# panel_power_backlight.net
KiCad netlist of a schematic drawn in Altium Designer
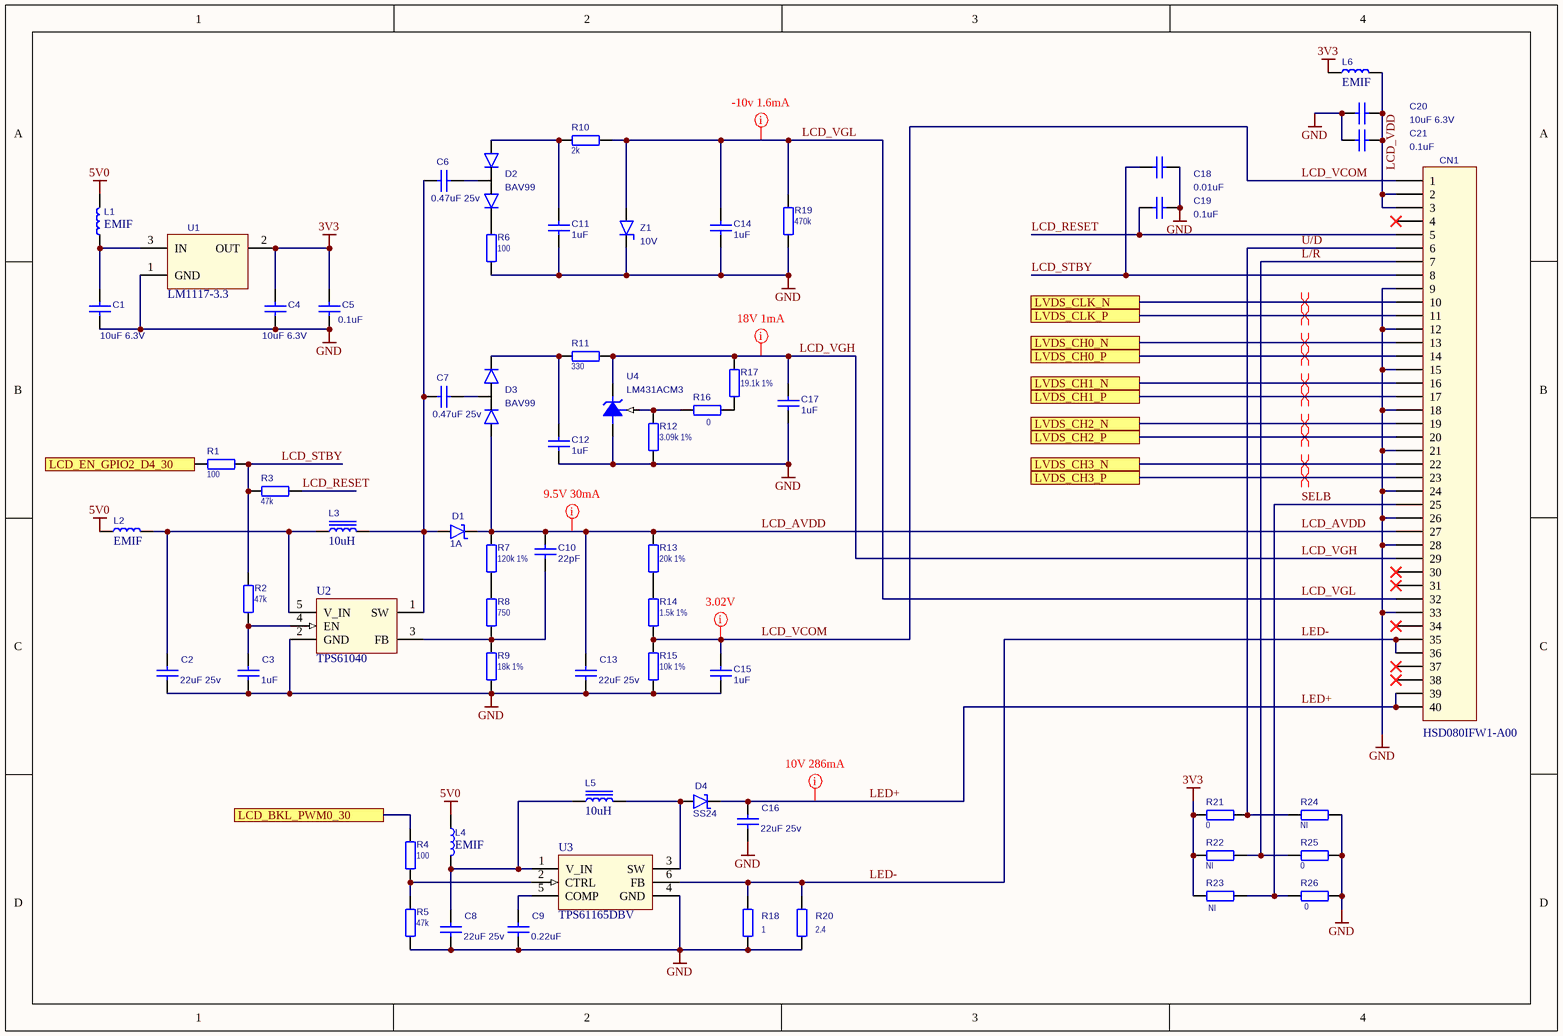
[diagram p0: panel_power_backlight.SchDoc]

(export (version "E")
  (design (tool "Eeschema 10.0.6"))
  (components
    (comp (ref "C1")
      (value "10uF 6.3V")
      (footprint "Capacitors:C0603")
      (description "CAP_NPOL")
      (fields (field (name "Comment") "CC0603MRX5R5BB106"))
      (libsource (lib "capacitors") (part "CAP_NPOL"))
    )
    (comp (ref "C2")
      (value "22uF 25v")
      (footprint "Capacitors:C0805")
      (description "CAP_NPOL")
      (fields (field (name "Comment") "CL21A226MAQNNNE"))
      (libsource (lib "capacitors") (part "CAP_NPOL"))
    )
    (comp (ref "C3")
      (value "1uF")
      (footprint "Capacitors:C0603")
      (description "CAP_NPOL")
      (fields (field (name "Comment") "CC0603KRX7R9BB105"))
      (libsource (lib "capacitors") (part "CAP_NPOL"))
    )
    (comp (ref "C4")
      (value "10uF 6.3V")
      (footprint "Capacitors:C0603")
      (description "CAP_NPOL")
      (fields (field (name "Comment") "CC0603MRX5R5BB106"))
      (libsource (lib "capacitors") (part "CAP_NPOL"))
    )
    (comp (ref "C5")
      (value "0.1uF")
      (footprint "C0603")
      (description "CAP_NPOL")
      (fields (field (name "Comment") "C1608X7R1H104K080AA"))
      (libsource (lib "capacitors") (part "CAP_NPOL"))
    )
    (comp (ref "C6")
      (value "0.47uF 25v")
      (footprint "Capacitors:C0603")
      (description "CAP_NPOL")
      (fields (field (name "Comment") "GRM188R71E474KA12D"))
      (libsource (lib "capacitors") (part "CAP_NPOL"))
    )
    (comp (ref "C7")
      (value "0.47uF 25v")
      (footprint "Capacitors:C0603")
      (description "CAP_NPOL")
      (fields (field (name "Comment") "GRM188R71E474KA12D"))
      (libsource (lib "capacitors") (part "CAP_NPOL"))
    )
    (comp (ref "C8")
      (value "22uF 25v")
      (footprint "Capacitors:C0805")
      (description "CAP_NPOL")
      (fields (field (name "Comment") "CL21A226MAQNNNE"))
      (libsource (lib "capacitors") (part "CAP_NPOL"))
    )
    (comp (ref "C9")
      (value "0.22uF")
      (footprint "Capacitors:C0603")
      (description "CAP_NPOL")
      (fields (field (name "Comment") "CC0603ZRY5V8BB224"))
      (libsource (lib "capacitors") (part "CAP_NPOL"))
    )
    (comp (ref "C10")
      (value "22pF")
      (footprint "Capacitors:C0603")
      (description "CAP_NPOL")
      (fields (field (name "Comment") "CL10C220JB8NNNC"))
      (libsource (lib "capacitors") (part "CAP_NPOL"))
    )
    (comp (ref "C11")
      (value "1uF")
      (footprint "C0603")
      (description "CAP_NPOL")
      (fields (field (name "Comment") "CC0603KRX7R9BB105"))
      (libsource (lib "capacitors") (part "CAP_NPOL"))
    )
    (comp (ref "C12")
      (value "1uF")
      (footprint "C0603")
      (description "CAP_NPOL")
      (fields (field (name "Comment") "CC0603KRX7R9BB105"))
      (libsource (lib "capacitors") (part "CAP_NPOL"))
    )
    (comp (ref "C13")
      (value "22uF 25v")
      (footprint "Capacitors:C0805")
      (description "CAP_NPOL")
      (fields (field (name "Comment") "CL21A226MAQNNNE"))
      (libsource (lib "capacitors") (part "CAP_NPOL"))
    )
    (comp (ref "C14")
      (value "1uF")
      (footprint "C0603")
      (description "CAP_NPOL")
      (fields (field (name "Comment") "CC0603KRX7R9BB105"))
      (libsource (lib "capacitors") (part "CAP_NPOL"))
    )
    (comp (ref "C15")
      (value "1uF")
      (footprint "C0603")
      (description "CAP_NPOL")
      (fields (field (name "Comment") "CC0603KRX7R9BB105"))
      (libsource (lib "capacitors") (part "CAP_NPOL"))
    )
    (comp (ref "C16")
      (value "22uF 25v")
      (footprint "Capacitors:C0805")
      (description "CAP_NPOL")
      (fields (field (name "Comment") "CL21A226MAQNNNE"))
      (libsource (lib "capacitors") (part "CAP_NPOL"))
    )
    (comp (ref "C17")
      (value "1uF")
      (footprint "C0603")
      (description "CAP_NPOL")
      (fields (field (name "Comment") "CC0603KRX7R9BB105"))
      (libsource (lib "capacitors") (part "CAP_NPOL"))
    )
    (comp (ref "C18")
      (value "0.01uF")
      (footprint "C0603")
      (description "CAP_NPOL")
      (fields (field (name "Comment") "CL10B103KB8NNNC"))
      (libsource (lib "capacitors") (part "CAP_NPOL"))
    )
    (comp (ref "C19")
      (value "0.1uF")
      (footprint "C0603")
      (description "CAP_NPOL")
      (fields (field (name "Comment") "C1608X7R1H104K080AA"))
      (libsource (lib "capacitors") (part "CAP_NPOL"))
    )
    (comp (ref "C20")
      (value "10uF 6.3V")
      (footprint "Capacitors:C0603")
      (description "CAP_NPOL")
      (fields (field (name "Comment") "CC0603MRX5R5BB106"))
      (libsource (lib "capacitors") (part "CAP_NPOL"))
    )
    (comp (ref "C21")
      (value "0.1uF")
      (footprint "C0603")
      (description "CAP_NPOL")
      (fields (field (name "Comment") "C1608X7R1H104K080AA"))
      (libsource (lib "capacitors") (part "CAP_NPOL"))
    )
    (comp (ref "CN1")
      (value "HSD080IFW1-A00")
      (footprint "40S-0.5SH")
      (description "DT38")
      (fields (field (name "Comment") "FH12-40"))
      (libsource (lib "FPC_FH12-40S-0.5SH") (part "FH12-40"))
    )
    (comp (ref "D1")
      (value "1A")
      (footprint "Diodes:SOD-323")
      (description "SHOTTKY")
      (fields (field (name "Comment") "PMEG2010EJ.115"))
      (libsource (lib "diodes") (part "SHOTTKY"))
    )
    (comp (ref "D2")
      (value "BAV99")
      (footprint "SOT-23-3")
      (description "Dual series 1")
      (fields (field (name "Comment") "BAV99.215"))
      (libsource (lib "diodes") (part "DIODE_DUAL_1"))
    )
    (comp (ref "D3")
      (value "BAV99")
      (footprint "SOT-23-3")
      (description "Dual series 1")
      (fields (field (name "Comment") "BAV99.215"))
      (libsource (lib "diodes") (part "DIODE_DUAL_1"))
    )
    (comp (ref "D4")
      (value "SS24")
      (footprint "SMA")
      (description "SHOTTKY")
      (libsource (lib "diodes") (part "SHOTTKY"))
    )
    (comp (ref "L1")
      (value "EMIF")
      (footprint "IND0805")
      (description "IND_WO_IRON")
      (fields (field (name "Comment") "BLM21PG221SN1D"))
      (libsource (lib "") (part "IND_WO_IRON_1"))
    )
    (comp (ref "L2")
      (value "EMIF")
      (footprint "IND0805")
      (description "IND_WO_IRON")
      (fields (field (name "Comment") "BLM21PG221SN1D"))
      (libsource (lib "inductors") (part "IND_WO_IRON"))
    )
    (comp (ref "L3")
      (value "10uH")
      (footprint "CDRH3D16")
      (description "IND_W_IRON")
      (fields (field (name "Comment") "CDRH3D16NP-100NC"))
      (libsource (lib "inductors") (part "IND_W_IRON"))
    )
    (comp (ref "L4")
      (value "EMIF")
      (footprint "IND0805")
      (description "IND_WO_IRON")
      (fields (field (name "Comment") "BLM21PG221SN1D"))
      (libsource (lib "inductors") (part "IND_WO_IRON"))
    )
    (comp (ref "L5")
      (value "10uH")
      (footprint "CDRH6D28")
      (description "IND_W_IRON")
      (fields (field (name "Comment") "CDRH6D28-100NC"))
      (libsource (lib "inductors") (part "IND_W_IRON"))
    )
    (comp (ref "L6")
      (value "EMIF")
      (footprint "IND0805")
      (description "IND_WO_IRON")
      (fields (field (name "Comment") "BLM21PG221SN1D"))
      (libsource (lib "") (part "IND_WO_IRON_1"))
    )
    (comp (ref "R1") (value "100") (footprint "R0603") (libsource (lib "resistors") (part "RESISTOR")))
    (comp (ref "R2")
      (value "47k")
      (footprint "R0603")
      (description "RES")
      (libsource (lib "resistors") (part "RESISTOR"))
    )
    (comp (ref "R3")
      (value "47k")
      (footprint "R0603")
      (description "RES")
      (libsource (lib "resistors") (part "RESISTOR"))
    )
    (comp (ref "R4") (value "100") (footprint "R0603") (libsource (lib "resistors") (part "RESISTOR")))
    (comp (ref "R5")
      (value "47k")
      (footprint "R0603")
      (description "RES")
      (libsource (lib "resistors") (part "RESISTOR"))
    )
    (comp (ref "R6")
      (value "100")
      (footprint "R0603")
      (description "RES")
      (libsource (lib "resistors") (part "RESISTOR"))
    )
    (comp (ref "R7")
      (value "120k 1%")
      (footprint "R0603")
      (description "RES")
      (fields (field (name "Comment") "120k"))
      (libsource (lib "resistors") (part "RESISTOR"))
    )
    (comp (ref "R8")
      (value "750")
      (footprint "R0603")
      (description "RES")
      (libsource (lib "resistors") (part "RESISTOR"))
    )
    (comp (ref "R9")
      (value "18k 1%")
      (footprint "R0603")
      (description "RES")
      (fields (field (name "Comment") "18k"))
      (libsource (lib "resistors") (part "RESISTOR"))
    )
    (comp (ref "R10")
      (value "2k")
      (footprint "R0603")
      (description "RES")
      (libsource (lib "resistors") (part "RESISTOR"))
    )
    (comp (ref "R11")
      (value "330")
      (footprint "R0603")
      (description "RES")
      (libsource (lib "resistors") (part "RESISTOR"))
    )
    (comp (ref "R12")
      (value "3.09k 1%")
      (footprint "R0603")
      (description "RES")
      (fields (field (name "Comment") "3.09k"))
      (libsource (lib "resistors") (part "RESISTOR"))
    )
    (comp (ref "R13")
      (value "20k 1%")
      (footprint "Resistors:R0603")
      (description "RES")
      (fields (field (name "Comment") "RC0603FR-0720KL"))
      (libsource (lib "resistors") (part "RESISTOR"))
    )
    (comp (ref "R14")
      (value "1.5k 1%")
      (footprint "R0603")
      (description "RES")
      (fields (field (name "Comment") "RC0603FR-071K5L"))
      (libsource (lib "resistors") (part "RESISTOR"))
    )
    (comp (ref "R15")
      (value "10k 1%")
      (footprint "R0603")
      (description "RES")
      (fields (field (name "Comment") "RC0603FR-0710KL"))
      (libsource (lib "resistors") (part "RESISTOR"))
    )
    (comp (ref "R16")
      (value "0")
      (footprint "R0603")
      (description "RES")
      (libsource (lib "resistors") (part "RESISTOR"))
    )
    (comp (ref "R17")
      (value "19.1k 1%")
      (footprint "R0603")
      (description "RES")
      (libsource (lib "resistors") (part "RESISTOR"))
    )
    (comp (ref "R18")
      (value "1")
      (footprint "R0805")
      (description "RES")
      (fields (field (name "Comment") "RC0805FR-071RL"))
      (libsource (lib "resistors") (part "RESISTOR"))
    )
    (comp (ref "R19")
      (value "470k")
      (footprint "R0603")
      (description "RES")
      (libsource (lib "resistors") (part "RESISTOR"))
    )
    (comp (ref "R20")
      (value "2.4")
      (footprint "R0805")
      (description "RES")
      (fields (field (name "Comment") "RES 0805 2R4 5%"))
      (libsource (lib "resistors") (part "RESISTOR"))
    )
    (comp (ref "R21")
      (value "0")
      (footprint "R0603")
      (description "RES")
      (libsource (lib "resistors") (part "RESISTOR"))
    )
    (comp (ref "R22")
      (value "NI")
      (footprint "R0603")
      (description "RES")
      (fields (field (name "Comment") "DNI"))
      (libsource (lib "resistors") (part "RESISTOR"))
    )
    (comp (ref "R23")
      (value "NI")
      (footprint "R0603")
      (description "RES")
      (fields (field (name "Comment") "DNI"))
      (libsource (lib "resistors") (part "RESISTOR"))
    )
    (comp (ref "R24")
      (value "NI")
      (footprint "R0603")
      (description "RES")
      (fields (field (name "Comment") "DNI"))
      (libsource (lib "resistors") (part "RESISTOR"))
    )
    (comp (ref "R25")
      (value "0")
      (footprint "R0603")
      (description "RES")
      (libsource (lib "resistors") (part "RESISTOR"))
    )
    (comp (ref "R26")
      (value "0")
      (footprint "R0603")
      (description "RES")
      (libsource (lib "resistors") (part "RESISTOR"))
    )
    (comp (ref "U1")
      (value "LM1117-3.3")
      (footprint "SOT-223")
      (description "LM1117")
      (libsource (lib "LM1117") (part "LM1117"))
    )
    (comp (ref "U2") (value "TPS61040") (footprint "SOT-23-5") (libsource (lib "TPS6104x") (part "TPS6104x")))
    (comp (ref "U3")
      (value "TPS61165DBV")
      (footprint "SOT-23-6")
      (description "TPS61165DBV (SOT-23-6 package)")
      (fields (field (name "Comment") "TPS61165"))
      (libsource (lib "TPS61165") (part "TPS61165DBV"))
    )
    (comp (ref "U4")
      (value "LM431ACM3")
      (footprint "SOT-23-3")
      (description "Adjustable Precision Zener Shunt Regulator, 3-pin SOT-23")
      (fields
        (field (name "MANUFACTURER") "National Semiconductor")
        (field (name "PUBLISHER") "Altium Limited")
      )
      (libsource (lib "NSC MiscPower") (part "LM431ACM3"))
    )
    (comp (ref "Z1")
      (value "10V")
      (footprint "SOD-80C")
      (description "ZENNER")
      (fields (field (name "Comment") "BZV55-C10.115"))
      (libsource (lib "diodes") (part "ZENNER"))
    )
  )
  (nets
    (net (code "1") (name "/LCD_AVDD") (class "Default")
      (node (ref "C10") (pin "1") (pinfunction "1_1") (pintype "passive"))
      (node (ref "C13") (pin "2") (pinfunction "2_2") (pintype "passive"))
      (node (ref "CN1") (pin "27") (pinfunction "27_27") (pintype "passive"))
      (node (ref "D1") (pin "2") (pinfunction "K_2") (pintype "passive"))
      (node (ref "D3") (pin "1") (pinfunction "A_1") (pintype "passive"))
      (node (ref "R13") (pin "2") (pinfunction "2_2") (pintype "passive"))
      (node (ref "R7") (pin "2") (pinfunction "2_2") (pintype "passive"))
    )
    (net (code "2") (name "/LCD_BKL_PWM0_30") (class "Default")
      (node (ref "R4") (pin "2") (pinfunction "2_2") (pintype "passive"))
    )
    (net (code "3") (name "/LCD_EN_GPIO2_D4_30") (class "Default")
      (node (ref "R1") (pin "2") (pinfunction "2_2") (pintype "passive"))
    )
    (net (code "4") (name "/LCD_RESET") (class "Default")
      (node (ref "C19") (pin "2") (pinfunction "2_2") (pintype "passive"))
      (node (ref "CN1") (pin "5") (pinfunction "5_5") (pintype "passive"))
      (node (ref "R3") (pin "1") (pinfunction "1_1") (pintype "passive"))
    )
    (net (code "5") (name "/LCD_STBY") (class "Default")
      (node (ref "C18") (pin "2") (pinfunction "2_2") (pintype "passive"))
      (node (ref "CN1") (pin "8") (pinfunction "8_8") (pintype "passive"))
      (node (ref "R1") (pin "1") (pinfunction "1_1") (pintype "passive"))
      (node (ref "R2") (pin "2") (pinfunction "2_2") (pintype "passive"))
      (node (ref "R3") (pin "2") (pinfunction "2_2") (pintype "passive"))
    )
    (net (code "6") (name "/LCD_VCOM") (class "Default")
      (node (ref "C15") (pin "2") (pinfunction "2_2") (pintype "passive"))
      (node (ref "CN1") (pin "1") (pinfunction "1_1") (pintype "passive"))
      (node (ref "R14") (pin "1") (pinfunction "1_1") (pintype "passive"))
      (node (ref "R15") (pin "2") (pinfunction "2_2") (pintype "passive"))
    )
    (net (code "7") (name "/LCD_VDD") (class "Default")
      (node (ref "C20") (pin "2") (pinfunction "2_2") (pintype "passive"))
      (node (ref "C21") (pin "1") (pinfunction "1_1") (pintype "passive"))
      (node (ref "CN1") (pin "2") (pinfunction "2_2") (pintype "passive"))
      (node (ref "CN1") (pin "3") (pinfunction "3_3") (pintype "passive"))
      (node (ref "L6") (pin "2") (pintype "passive"))
    )
    (net (code "8") (name "/LCD_VGH") (class "Default")
      (node (ref "C17") (pin "2") (pinfunction "2_2") (pintype "passive"))
      (node (ref "CN1") (pin "29") (pinfunction "29_29") (pintype "passive"))
      (node (ref "R11") (pin "2") (pinfunction "2_2") (pintype "passive"))
      (node (ref "R17") (pin "2") (pinfunction "2_2") (pintype "passive"))
      (node (ref "U4") (pin "1") (pinfunction "K_1") (pintype "passive"))
    )
    (net (code "9") (name "/LCD_VGL") (class "Default")
      (node (ref "C14") (pin "2") (pinfunction "2_2") (pintype "passive"))
      (node (ref "CN1") (pin "32") (pinfunction "32_32") (pintype "passive"))
      (node (ref "R10") (pin "2") (pinfunction "2_2") (pintype "passive"))
      (node (ref "R19") (pin "2") (pinfunction "2_2") (pintype "passive"))
      (node (ref "Z1") (pin "1") (pinfunction "A_1") (pintype "passive"))
    )
    (net (code "10") (name "/LED+") (class "Default")
      (node (ref "C16") (pin "2") (pinfunction "2_2") (pintype "passive"))
      (node (ref "CN1") (pin "39") (pinfunction "39_39") (pintype "passive"))
      (node (ref "CN1") (pin "40") (pinfunction "40_40") (pintype "passive"))
      (node (ref "D4") (pin "2") (pinfunction "K_2") (pintype "passive"))
    )
    (net (code "11") (name "/LED-") (class "Default")
      (node (ref "CN1") (pin "35") (pinfunction "35_35") (pintype "passive"))
      (node (ref "CN1") (pin "36") (pinfunction "36_36") (pintype "passive"))
      (node (ref "R18") (pin "2") (pinfunction "2_2") (pintype "passive"))
      (node (ref "R20") (pin "2") (pinfunction "2_2") (pintype "passive"))
      (node (ref "U3") (pin "6") (pinfunction "FB_6") (pintype "passive"))
    )
    (net (code "12") (name "/LVDS_CH0_N") (class "Default")
      (node (ref "CN1") (pin "13") (pinfunction "13_13") (pintype "passive"))
    )
    (net (code "13") (name "/LVDS_CH0_P") (class "Default")
      (node (ref "CN1") (pin "14") (pinfunction "14_14") (pintype "passive"))
    )
    (net (code "14") (name "/LVDS_CH1_N") (class "Default")
      (node (ref "CN1") (pin "16") (pinfunction "16_16") (pintype "passive"))
    )
    (net (code "15") (name "/LVDS_CH1_P") (class "Default")
      (node (ref "CN1") (pin "17") (pinfunction "17_17") (pintype "passive"))
    )
    (net (code "16") (name "/LVDS_CH2_N") (class "Default")
      (node (ref "CN1") (pin "19") (pinfunction "19_19") (pintype "passive"))
    )
    (net (code "17") (name "/LVDS_CH2_P") (class "Default")
      (node (ref "CN1") (pin "20") (pinfunction "20_20") (pintype "passive"))
    )
    (net (code "18") (name "/LVDS_CH3_N") (class "Default")
      (node (ref "CN1") (pin "22") (pinfunction "22_22") (pintype "passive"))
    )
    (net (code "19") (name "/LVDS_CH3_P") (class "Default")
      (node (ref "CN1") (pin "23") (pinfunction "23_23") (pintype "passive"))
    )
    (net (code "20") (name "/LVDS_CLK_N") (class "Default")
      (node (ref "CN1") (pin "10") (pinfunction "10_10") (pintype "passive"))
    )
    (net (code "21") (name "/LVDS_CLK_P") (class "Default")
      (node (ref "CN1") (pin "11") (pinfunction "11_11") (pintype "passive"))
    )
    (net (code "22") (name "/L{slash}R") (class "Default")
      (node (ref "CN1") (pin "7") (pinfunction "7_7") (pintype "passive"))
      (node (ref "R22") (pin "2") (pinfunction "2_2") (pintype "passive"))
      (node (ref "R25") (pin "1") (pinfunction "1_1") (pintype "passive"))
    )
    (net (code "23") (name "/SELB") (class "Default")
      (node (ref "CN1") (pin "25") (pinfunction "25_25") (pintype "passive"))
      (node (ref "R23") (pin "2") (pinfunction "2_2") (pintype "passive"))
      (node (ref "R26") (pin "1") (pinfunction "1_1") (pintype "passive"))
    )
    (net (code "24") (name "/U{slash}D") (class "Default")
      (node (ref "CN1") (pin "6") (pinfunction "6_6") (pintype "passive"))
      (node (ref "R21") (pin "2") (pinfunction "2_2") (pintype "passive"))
      (node (ref "R24") (pin "1") (pinfunction "1_1") (pintype "passive"))
    )
    (net (code "25") (name "3V3") (class "Default")
      (node (ref "C4") (pin "1") (pinfunction "1_1") (pintype "passive"))
      (node (ref "C5") (pin "2") (pinfunction "2_2") (pintype "passive"))
      (node (ref "L6") (pin "1") (pintype "passive"))
      (node (ref "R21") (pin "1") (pinfunction "1_1") (pintype "passive"))
      (node (ref "R22") (pin "1") (pinfunction "1_1") (pintype "passive"))
      (node (ref "R23") (pin "1") (pinfunction "1_1") (pintype "passive"))
      (node (ref "U1") (pin "2") (pinfunction "OUT_2") (pintype "passive"))
    )
    (net (code "26") (name "5V0") (class "Default")
      (node (ref "L1") (pin "2") (pintype "passive"))
      (node (ref "L2") (pin "2") (pintype "passive"))
      (node (ref "L4") (pin "2") (pintype "passive"))
    )
    (net (code "27") (name "GND") (class "Default")
      (node (ref "C1") (pin "2") (pinfunction "2_2") (pintype "passive"))
      (node (ref "C11") (pin "1") (pinfunction "1_1") (pintype "passive"))
      (node (ref "C12") (pin "1") (pinfunction "1_1") (pintype "passive"))
      (node (ref "C13") (pin "1") (pinfunction "1_1") (pintype "passive"))
      (node (ref "C14") (pin "1") (pinfunction "1_1") (pintype "passive"))
      (node (ref "C15") (pin "1") (pinfunction "1_1") (pintype "passive"))
      (node (ref "C16") (pin "1") (pinfunction "1_1") (pintype "passive"))
      (node (ref "C17") (pin "1") (pinfunction "1_1") (pintype "passive"))
      (node (ref "C18") (pin "1") (pinfunction "1_1") (pintype "passive"))
      (node (ref "C19") (pin "1") (pinfunction "1_1") (pintype "passive"))
      (node (ref "C2") (pin "1") (pinfunction "1_1") (pintype "passive"))
      (node (ref "C20") (pin "1") (pinfunction "1_1") (pintype "passive"))
      (node (ref "C21") (pin "2") (pinfunction "2_2") (pintype "passive"))
      (node (ref "C3") (pin "1") (pinfunction "1_1") (pintype "passive"))
      (node (ref "C4") (pin "2") (pinfunction "2_2") (pintype "passive"))
      (node (ref "C5") (pin "1") (pinfunction "1_1") (pintype "passive"))
      (node (ref "C8") (pin "1") (pinfunction "1_1") (pintype "passive"))
      (node (ref "C9") (pin "1") (pinfunction "1_1") (pintype "passive"))
      (node (ref "CN1") (pin "12") (pinfunction "12_12") (pintype "passive"))
      (node (ref "CN1") (pin "15") (pinfunction "15_15") (pintype "passive"))
      (node (ref "CN1") (pin "18") (pinfunction "18_18") (pintype "passive"))
      (node (ref "CN1") (pin "21") (pinfunction "21_21") (pintype "passive"))
      (node (ref "CN1") (pin "24") (pinfunction "24_24") (pintype "passive"))
      (node (ref "CN1") (pin "26") (pinfunction "26_26") (pintype "passive"))
      (node (ref "CN1") (pin "28") (pinfunction "28_28") (pintype "passive"))
      (node (ref "CN1") (pin "33") (pinfunction "33_33") (pintype "passive"))
      (node (ref "CN1") (pin "9") (pinfunction "9_9") (pintype "passive"))
      (node (ref "R12") (pin "1") (pinfunction "1_1") (pintype "passive"))
      (node (ref "R15") (pin "1") (pinfunction "1_1") (pintype "passive"))
      (node (ref "R18") (pin "1") (pinfunction "1_1") (pintype "passive"))
      (node (ref "R19") (pin "1") (pinfunction "1_1") (pintype "passive"))
      (node (ref "R20") (pin "1") (pinfunction "1_1") (pintype "passive"))
      (node (ref "R24") (pin "2") (pinfunction "2_2") (pintype "passive"))
      (node (ref "R25") (pin "2") (pinfunction "2_2") (pintype "passive"))
      (node (ref "R26") (pin "2") (pinfunction "2_2") (pintype "passive"))
      (node (ref "R5") (pin "1") (pinfunction "1_1") (pintype "passive"))
      (node (ref "R6") (pin "2") (pinfunction "2_2") (pintype "passive"))
      (node (ref "R9") (pin "1") (pinfunction "1_1") (pintype "passive"))
      (node (ref "U1") (pin "1") (pinfunction "GND_1") (pintype "passive"))
      (node (ref "U2") (pin "2") (pinfunction "GND_2") (pintype "power_in"))
      (node (ref "U3") (pin "4") (pinfunction "GND_4") (pintype "power_in"))
      (node (ref "U4") (pin "3") (pinfunction "A_3") (pintype "passive"))
      (node (ref "Z1") (pin "2") (pinfunction "K_2") (pintype "passive"))
    )
    (net (code "28") (name "Net-(D1-A)") (class "Default")
      (node (ref "C6") (pin "2") (pinfunction "2_2") (pintype "passive"))
      (node (ref "C7") (pin "2") (pinfunction "2_2") (pintype "passive"))
      (node (ref "D1") (pin "1") (pinfunction "A_1") (pintype "passive"))
      (node (ref "L3") (pin "2") (pintype "passive"))
      (node (ref "U2") (pin "1") (pinfunction "SW_1") (pintype "passive"))
    )
    (net (code "29") (name "Net-(D2-A)") (class "Default")
      (node (ref "C11") (pin "2") (pinfunction "2_2") (pintype "passive"))
      (node (ref "D2") (pin "1") (pinfunction "A_1") (pintype "passive"))
      (node (ref "R10") (pin "1") (pinfunction "1_1") (pintype "passive"))
    )
    (net (code "30") (name "Net-(D2-A+K)") (class "Default")
      (node (ref "C6") (pin "1") (pinfunction "1_1") (pintype "passive"))
      (node (ref "D2") (pin "3") (pinfunction "A+K_3") (pintype "passive"))
    )
    (net (code "31") (name "Net-(D2-K)") (class "Default")
      (node (ref "D2") (pin "2") (pinfunction "K_2") (pintype "passive"))
      (node (ref "R6") (pin "1") (pinfunction "1_1") (pintype "passive"))
    )
    (net (code "32") (name "Net-(D3-A+K)") (class "Default")
      (node (ref "C7") (pin "1") (pinfunction "1_1") (pintype "passive"))
      (node (ref "D3") (pin "3") (pinfunction "A+K_3") (pintype "passive"))
    )
    (net (code "33") (name "Net-(D3-K)") (class "Default")
      (node (ref "C12") (pin "2") (pinfunction "2_2") (pintype "passive"))
      (node (ref "D3") (pin "2") (pinfunction "K_2") (pintype "passive"))
      (node (ref "R11") (pin "1") (pinfunction "1_1") (pintype "passive"))
    )
    (net (code "34") (name "Net-(D4-A)") (class "Default")
      (node (ref "D4") (pin "1") (pinfunction "A_1") (pintype "passive"))
      (node (ref "L5") (pin "2") (pintype "passive"))
      (node (ref "U3") (pin "3") (pinfunction "SW_3") (pintype "passive"))
    )
    (net (code "35") (name "Net-(R7-Pad1)") (class "Default")
      (node (ref "R7") (pin "1") (pinfunction "1_1") (pintype "passive"))
      (node (ref "R8") (pin "2") (pinfunction "2_2") (pintype "passive"))
    )
    (net (code "36") (name "Net-(R13-Pad1)") (class "Default")
      (node (ref "R13") (pin "1") (pinfunction "1_1") (pintype "passive"))
      (node (ref "R14") (pin "2") (pinfunction "2_2") (pintype "passive"))
    )
    (net (code "37") (name "Net-(R16-Pad1)") (class "Default")
      (node (ref "R16") (pin "1") (pinfunction "1_1") (pintype "passive"))
      (node (ref "R17") (pin "1") (pinfunction "1_1") (pintype "passive"))
    )
    (net (code "38") (name "Net-(U1-IN)") (class "Default")
      (node (ref "C1") (pin "1") (pinfunction "1_1") (pintype "passive"))
      (node (ref "L1") (pin "1") (pintype "passive"))
      (node (ref "U1") (pin "3") (pinfunction "IN_3") (pintype "passive"))
    )
    (net (code "39") (name "Net-(U2-EN)") (class "Default")
      (node (ref "C3") (pin "2") (pinfunction "2_2") (pintype "passive"))
      (node (ref "R2") (pin "1") (pinfunction "1_1") (pintype "passive"))
      (node (ref "U2") (pin "4") (pinfunction "EN_4") (pintype "input"))
    )
    (net (code "40") (name "Net-(U2-FB)") (class "Default")
      (node (ref "C10") (pin "2") (pinfunction "2_2") (pintype "passive"))
      (node (ref "R8") (pin "1") (pinfunction "1_1") (pintype "passive"))
      (node (ref "R9") (pin "2") (pinfunction "2_2") (pintype "passive"))
      (node (ref "U2") (pin "3") (pinfunction "FB_3") (pintype "passive"))
    )
    (net (code "41") (name "Net-(U2-V_IN)") (class "Default")
      (node (ref "C2") (pin "2") (pinfunction "2_2") (pintype "passive"))
      (node (ref "L2") (pin "1") (pintype "passive"))
      (node (ref "L3") (pin "1") (pintype "passive"))
      (node (ref "U2") (pin "5") (pinfunction "V_IN_5") (pintype "power_in"))
    )
    (net (code "42") (name "Net-(U3-COMP)") (class "Default")
      (node (ref "C9") (pin "2") (pinfunction "2_2") (pintype "passive"))
      (node (ref "U3") (pin "5") (pinfunction "COMP_5") (pintype "passive"))
    )
    (net (code "43") (name "Net-(U3-CTRL)") (class "Default")
      (node (ref "R4") (pin "1") (pinfunction "1_1") (pintype "passive"))
      (node (ref "R5") (pin "2") (pinfunction "2_2") (pintype "passive"))
      (node (ref "U3") (pin "2") (pinfunction "CTRL_2") (pintype "input"))
    )
    (net (code "44") (name "Net-(U3-V_IN)") (class "Default")
      (node (ref "C8") (pin "2") (pinfunction "2_2") (pintype "passive"))
      (node (ref "L4") (pin "1") (pintype "passive"))
      (node (ref "L5") (pin "1") (pintype "passive"))
      (node (ref "U3") (pin "1") (pinfunction "V_IN_1") (pintype "power_in"))
    )
    (net (code "45") (name "Net-(U4-REF)") (class "Default")
      (node (ref "R12") (pin "2") (pinfunction "2_2") (pintype "passive"))
      (node (ref "R16") (pin "2") (pinfunction "2_2") (pintype "passive"))
      (node (ref "U4") (pin "2") (pinfunction "REF_2") (pintype "input"))
    )
    (net (code "46") (name "unconnected-(CN1-Pad4)") (class "Default")
      (node (ref "CN1") (pin "4") (pinfunction "4_4") (pintype "passive+no_connect"))
    )
    (net (code "47") (name "unconnected-(CN1-Pad30)") (class "Default")
      (node (ref "CN1") (pin "30") (pinfunction "30_30") (pintype "passive+no_connect"))
    )
    (net (code "48") (name "unconnected-(CN1-Pad31)") (class "Default")
      (node (ref "CN1") (pin "31") (pinfunction "31_31") (pintype "passive+no_connect"))
    )
    (net (code "49") (name "unconnected-(CN1-Pad34)") (class "Default")
      (node (ref "CN1") (pin "34") (pinfunction "34_34") (pintype "passive+no_connect"))
    )
    (net (code "50") (name "unconnected-(CN1-Pad37)") (class "Default")
      (node (ref "CN1") (pin "37") (pinfunction "37_37") (pintype "passive+no_connect"))
    )
    (net (code "51") (name "unconnected-(CN1-Pad38)") (class "Default")
      (node (ref "CN1") (pin "38") (pinfunction "38_38") (pintype "passive+no_connect"))
    )
  )
)
